# 6_channel_esp32_energy_meter_add-on.net
KiCad netlist of a schematic drawn in EAGLE
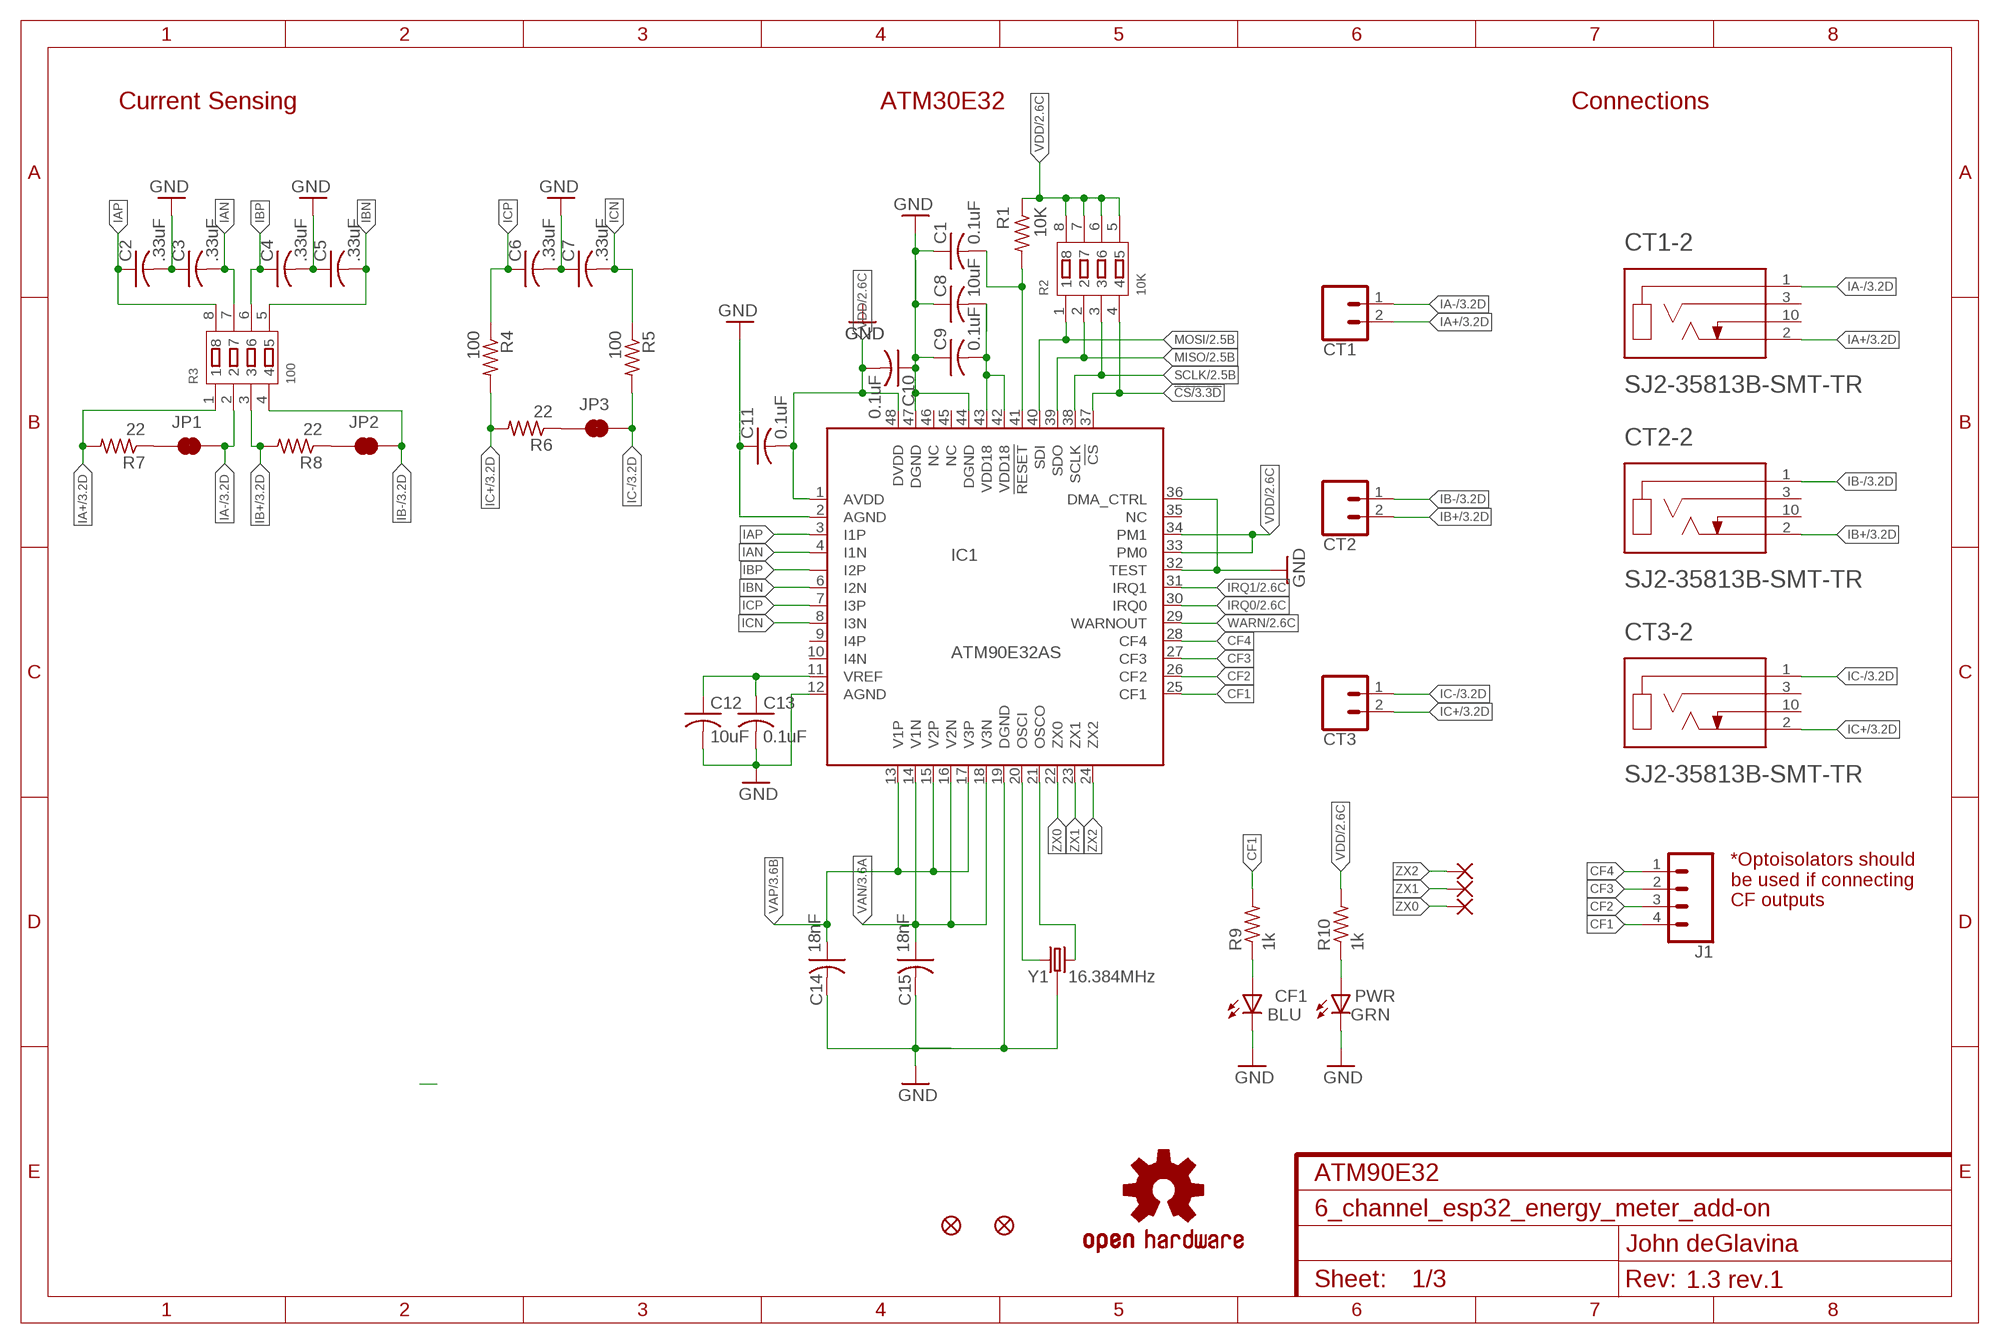
[diagram p0: schematic, sheet 1]
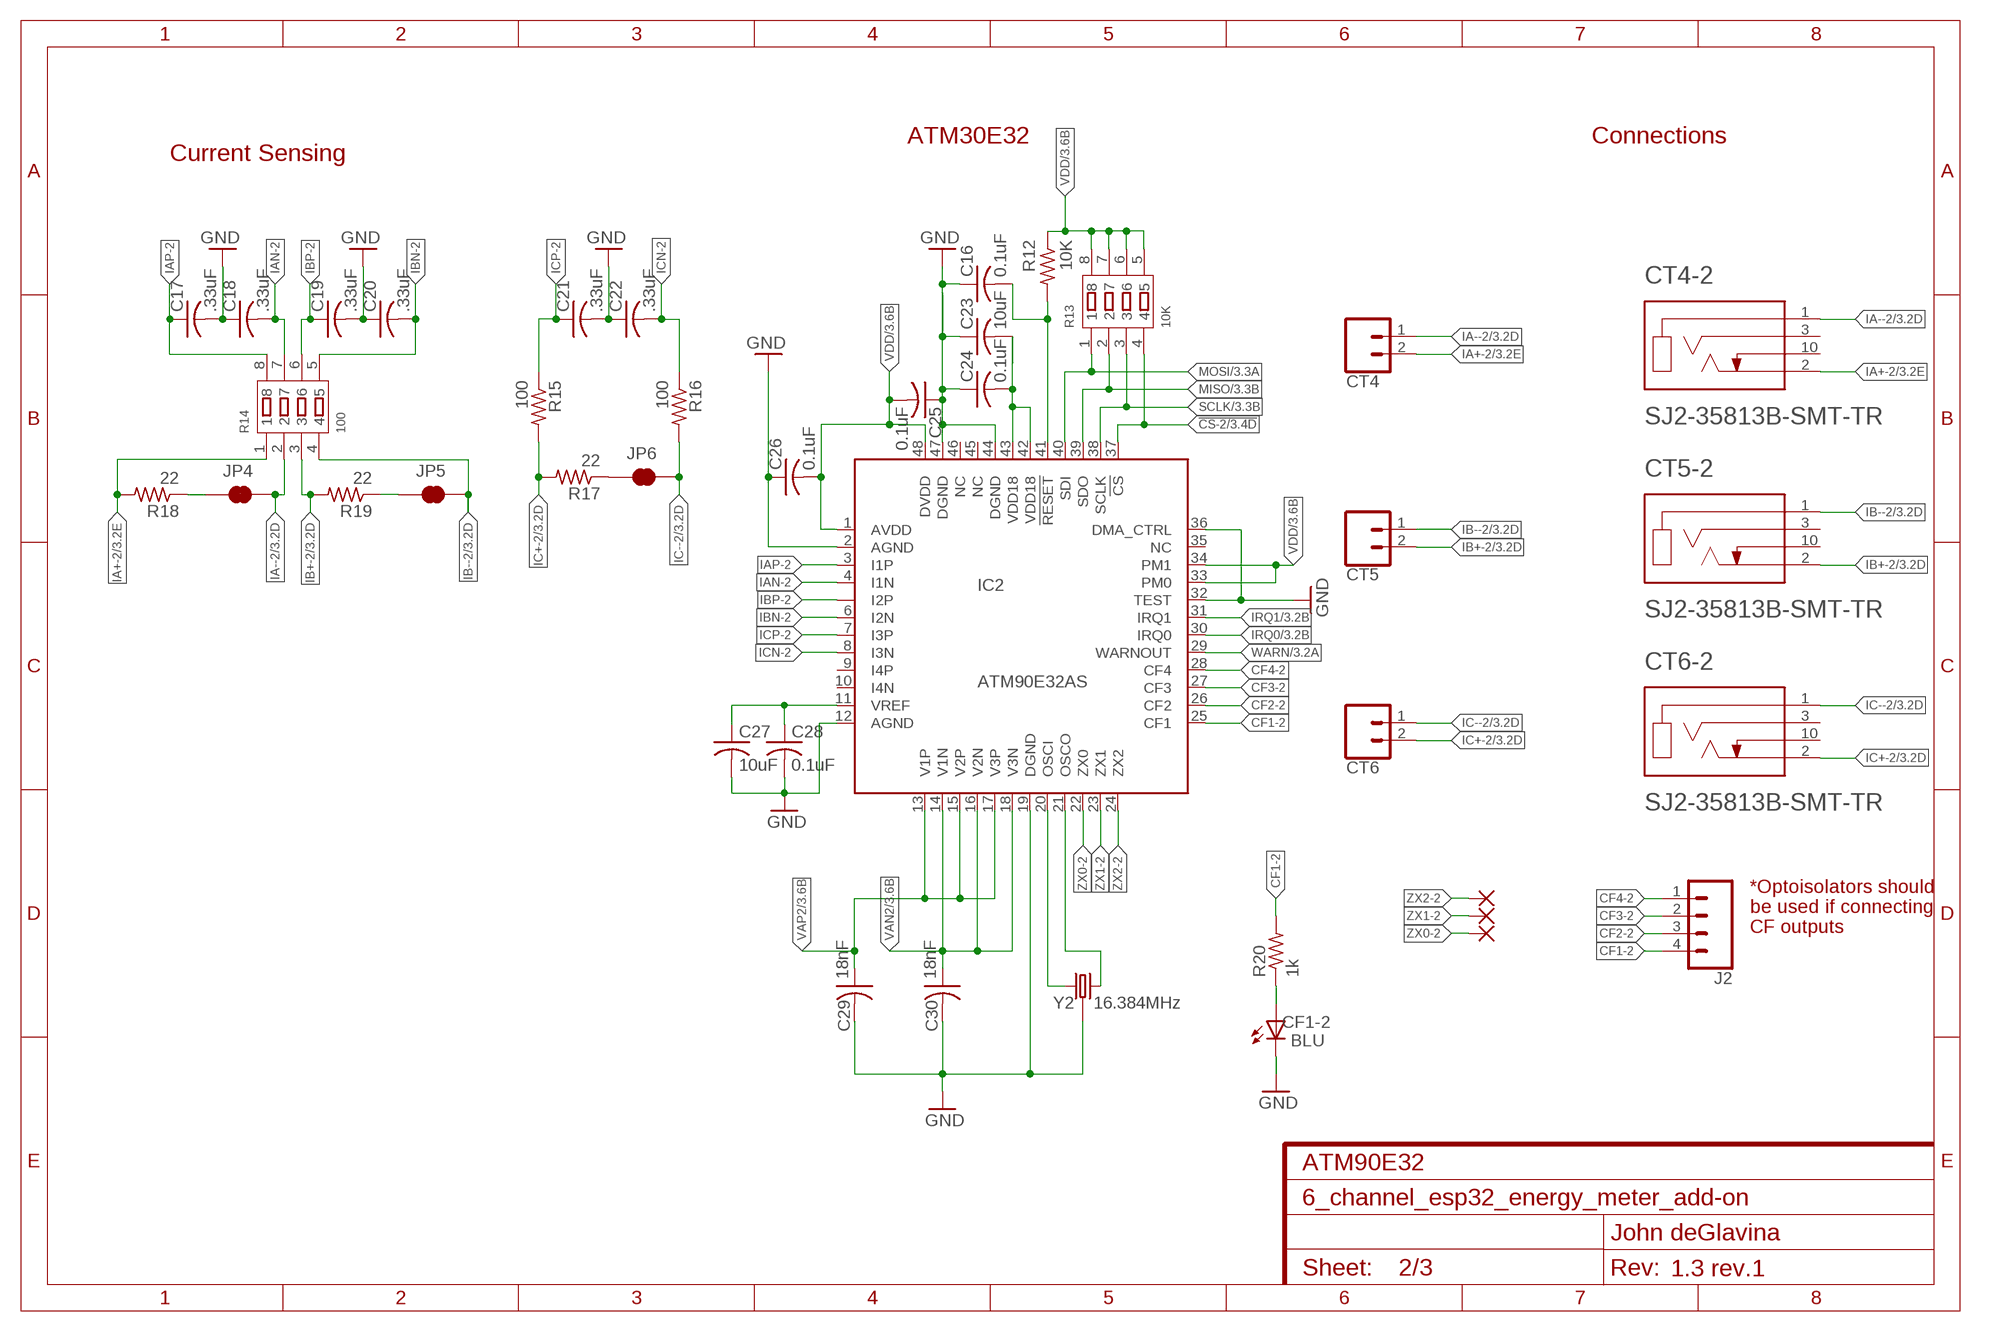
[diagram p1: schematic, sheet 2]
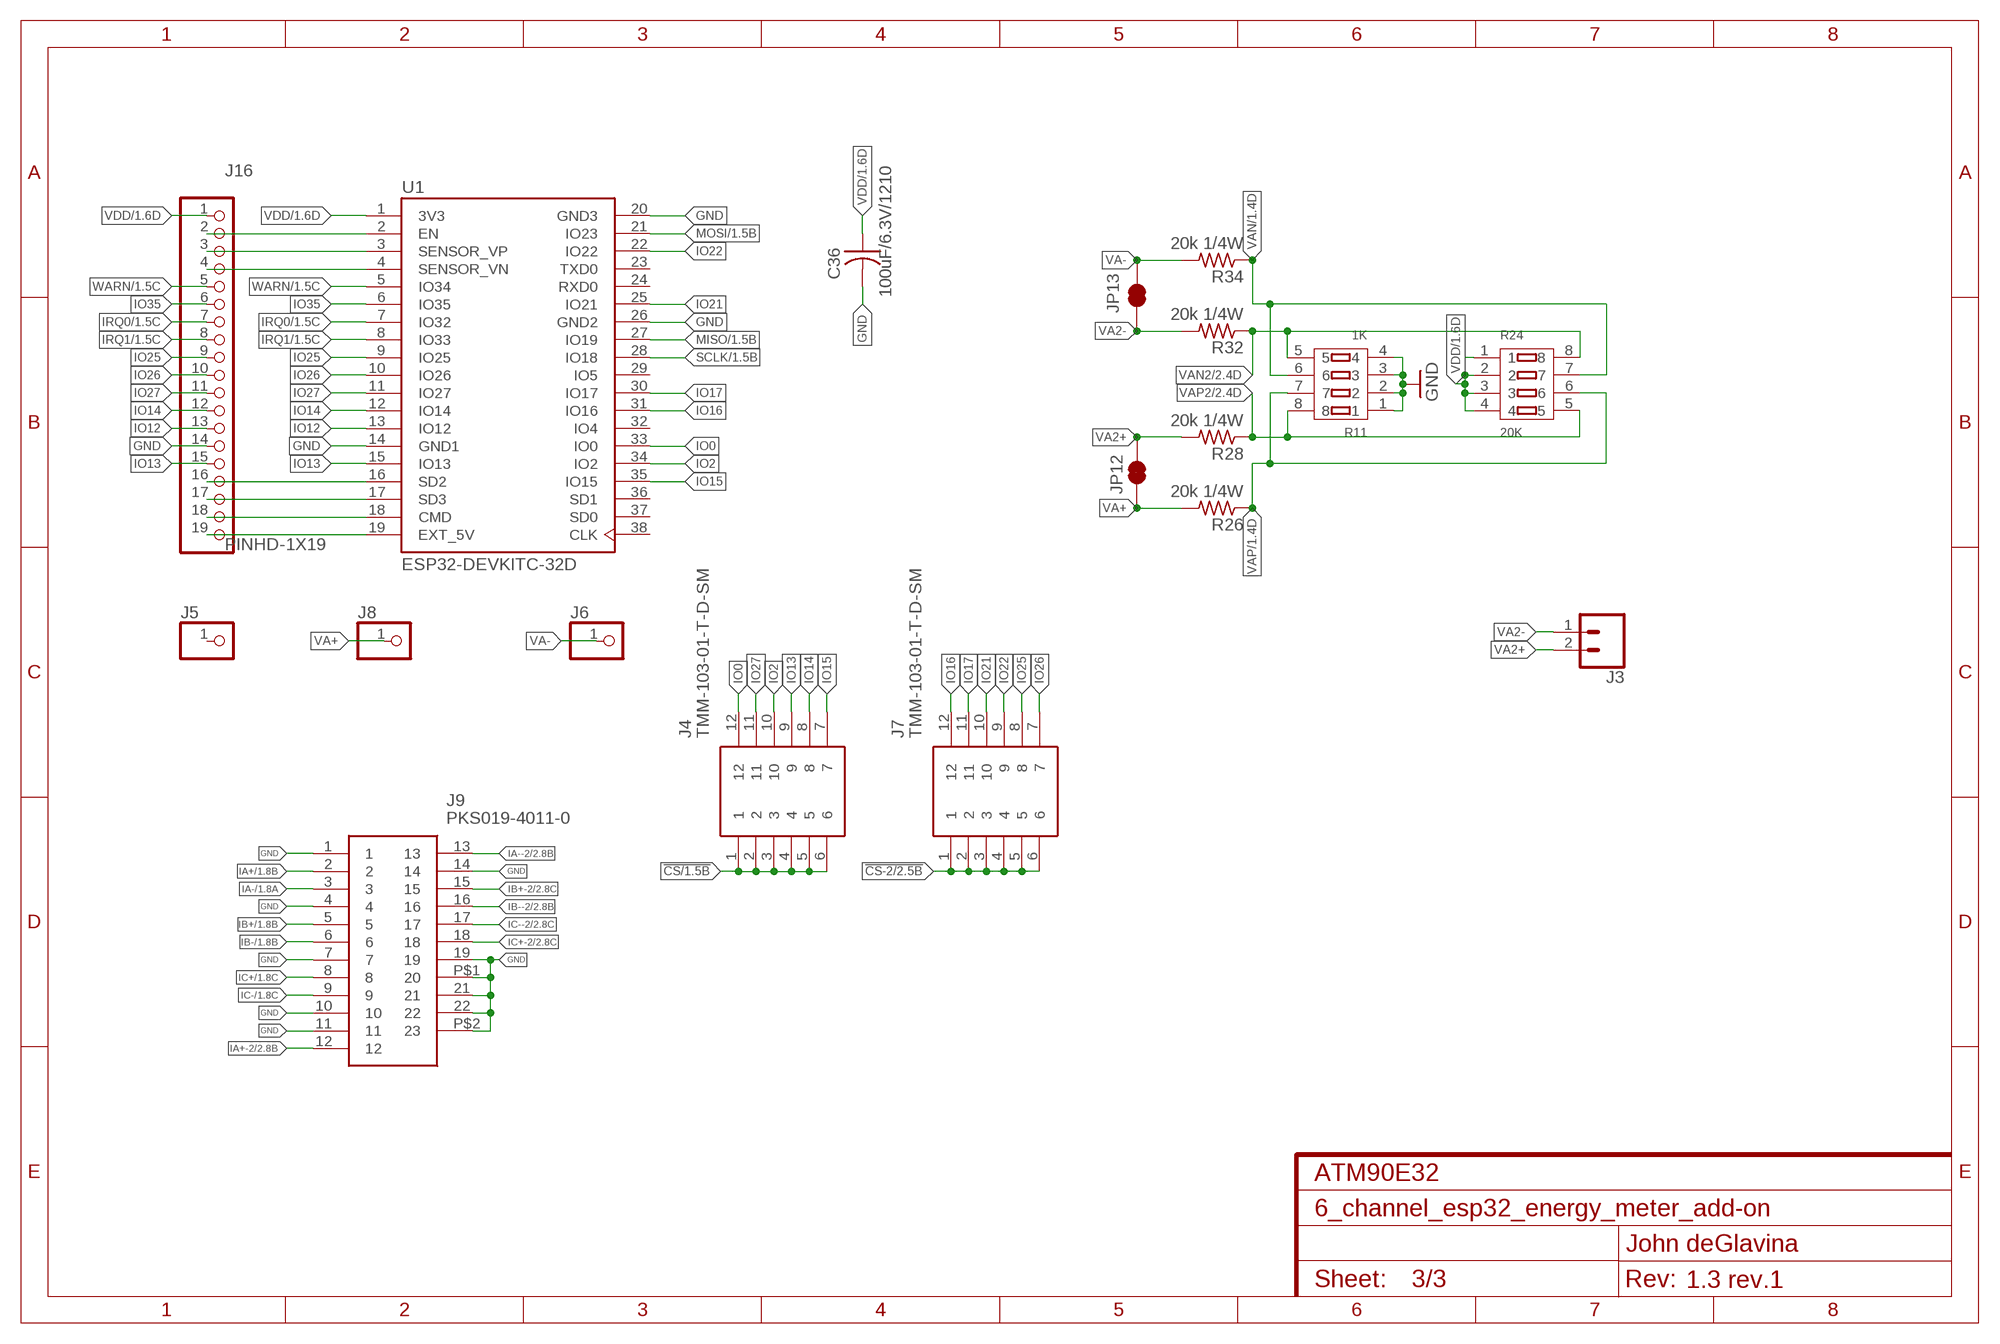
[diagram p2: schematic, sheet 3]

(export (version "E")
  (design (tool "Eeschema 10.0.6"))
  (components
    (comp (ref "C16")
      (value "0.1uF")
      (footprint "eagle-import:C0603")
      (libsource (lib "eagle-import") (part "C-USC0603"))
    )
    (comp (ref "C17")
      (value ".33uF")
      (footprint "eagle-import:C0603")
      (libsource (lib "eagle-import") (part "C-USC0603"))
    )
    (comp (ref "C18")
      (value ".33uF")
      (footprint "eagle-import:C0603")
      (libsource (lib "eagle-import") (part "C-USC0603"))
    )
    (comp (ref "C19")
      (value ".33uF")
      (footprint "eagle-import:C0603")
      (libsource (lib "eagle-import") (part "C-USC0603"))
    )
    (comp (ref "C20")
      (value ".33uF")
      (footprint "eagle-import:C0603")
      (libsource (lib "eagle-import") (part "C-USC0603"))
    )
    (comp (ref "C21")
      (value ".33uF")
      (footprint "eagle-import:C0603")
      (libsource (lib "eagle-import") (part "C-USC0603"))
    )
    (comp (ref "C22")
      (value ".33uF")
      (footprint "eagle-import:C0603")
      (libsource (lib "eagle-import") (part "C-USC0603"))
    )
    (comp (ref "C23")
      (value "10uF")
      (footprint "eagle-import:C0603")
      (libsource (lib "eagle-import") (part "C-USC0603"))
    )
    (comp (ref "C24")
      (value "0.1uF")
      (footprint "eagle-import:C0603")
      (libsource (lib "eagle-import") (part "C-USC0603"))
    )
    (comp (ref "C25")
      (value "0.1uF")
      (footprint "eagle-import:C0603")
      (libsource (lib "eagle-import") (part "C-USC0603"))
    )
    (comp (ref "C26")
      (value "0.1uF")
      (footprint "eagle-import:C0603")
      (libsource (lib "eagle-import") (part "C-USC0603"))
    )
    (comp (ref "C27")
      (value "10uF")
      (footprint "eagle-import:C0603")
      (libsource (lib "eagle-import") (part "C-USC0603"))
    )
    (comp (ref "C28")
      (value "0.1uF")
      (footprint "eagle-import:C0603")
      (libsource (lib "eagle-import") (part "C-USC0603"))
    )
    (comp (ref "C29")
      (value "18nF")
      (footprint "eagle-import:C0603")
      (libsource (lib "eagle-import") (part "C-USC0603"))
    )
    (comp (ref "C30")
      (value "18nF")
      (footprint "eagle-import:C0603")
      (libsource (lib "eagle-import") (part "C-USC0603"))
    )
    (comp (ref "CF1-2")
      (value "BLU")
      (footprint "eagle-import:CHIPLED_0603")
      (libsource (lib "eagle-import") (part "LEDCHIPLED_0603"))
    )
    (comp (ref "CT4")
      (value "CONN_023.5MM")
      (footprint "eagle-import:SCREWTERMINAL-3.5MM-2")
      (libsource (lib "eagle-import") (part "SparkFun-Connectors_8231346_CONN_023.5MM"))
    )
    (comp (ref "CT4-2")
      (value "SJ2-35813B-SMT-TR")
      (footprint "eagle-import:CUI_SJ2-35813B-SMT-TR")
      (fields (field (name "MANUFACTURER") "CUI"))
      (libsource (lib "eagle-import") (part "SJ2-35813B-SMT-TR"))
    )
    (comp (ref "CT5")
      (value "CONN_023.5MM")
      (footprint "eagle-import:SCREWTERMINAL-3.5MM-2")
      (libsource (lib "eagle-import") (part "SparkFun-Connectors_8231346_CONN_023.5MM"))
    )
    (comp (ref "CT5-2")
      (value "SJ2-35813B-SMT-TR")
      (footprint "eagle-import:CUI_SJ2-35813B-SMT-TR")
      (fields (field (name "MANUFACTURER") "CUI"))
      (libsource (lib "eagle-import") (part "SJ2-35813B-SMT-TR"))
    )
    (comp (ref "CT6")
      (value "CONN_023.5MM")
      (footprint "eagle-import:SCREWTERMINAL-3.5MM-2")
      (libsource (lib "eagle-import") (part "SparkFun-Connectors_8231346_CONN_023.5MM"))
    )
    (comp (ref "CT6-2")
      (value "SJ2-35813B-SMT-TR")
      (footprint "eagle-import:CUI_SJ2-35813B-SMT-TR")
      (fields (field (name "MANUFACTURER") "CUI"))
      (libsource (lib "eagle-import") (part "SJ2-35813B-SMT-TR"))
    )
    (comp (ref "IC2")
      (value "ATM90E32AS")
      (footprint "eagle-import:QFP50P900X900X120-48")
      (fields (field (name "SPICEPREFIX") "X"))
      (libsource (lib "eagle-import") (part "ATM90E36"))
    )
    (comp (ref "J2")
      (value "CONN_04")
      (footprint "eagle-import:1X04")
      (libsource (lib "eagle-import") (part "CONN_04"))
    )
    (comp (ref "JP4")
      (value "JUMPER-SMT_2_NC_TRACE_SILK")
      (footprint "eagle-import:SMT-JUMPER_2_NC_TRACE_SILK")
      (libsource (lib "eagle-import") (part "JUMPER-SMT_2_NC_TRACE_SILK"))
    )
    (comp (ref "JP5")
      (value "JUMPER-SMT_2_NC_TRACE_SILK")
      (footprint "eagle-import:SMT-JUMPER_2_NC_TRACE_SILK")
      (libsource (lib "eagle-import") (part "JUMPER-SMT_2_NC_TRACE_SILK"))
    )
    (comp (ref "JP6")
      (value "JUMPER-SMT_2_NC_TRACE_SILK")
      (footprint "eagle-import:SMT-JUMPER_2_NC_TRACE_SILK")
      (libsource (lib "eagle-import") (part "JUMPER-SMT_2_NC_TRACE_SILK"))
    )
    (comp (ref "R12")
      (value "10K")
      (footprint "eagle-import:R0603")
      (libsource (lib "eagle-import") (part "R-US_R0603"))
    )
    (comp (ref "R13")
      (value "10K")
      (footprint "eagle-import:RA1206-8")
      (fields (field (name "MPN") "Chip-Array-Series-1%"))
      (libsource (lib "eagle-import") (part "SMD-RES-ARRAY-1K-4R(RA1206-8)"))
    )
    (comp (ref "R14")
      (value "100")
      (footprint "eagle-import:RA1206-8")
      (fields (field (name "MPN") "Chip-Array-Series-1%"))
      (libsource (lib "eagle-import") (part "SMD-RES-ARRAY-1K-4R(RA1206-8)"))
    )
    (comp (ref "R15")
      (value "100")
      (footprint "eagle-import:R0603")
      (libsource (lib "eagle-import") (part "R-US_R0603"))
    )
    (comp (ref "R16")
      (value "100")
      (footprint "eagle-import:R0603")
      (libsource (lib "eagle-import") (part "R-US_R0603"))
    )
    (comp (ref "R17")
      (value "22")
      (footprint "eagle-import:R0603")
      (libsource (lib "eagle-import") (part "R-US_R0603"))
    )
    (comp (ref "R18")
      (value "22")
      (footprint "eagle-import:R0603")
      (libsource (lib "eagle-import") (part "R-US_R0603"))
    )
    (comp (ref "R19")
      (value "22")
      (footprint "eagle-import:R0603")
      (libsource (lib "eagle-import") (part "R-US_R0603"))
    )
    (comp (ref "R20")
      (value "1k")
      (footprint "eagle-import:R0603")
      (libsource (lib "eagle-import") (part "R-US_R0603"))
    )
    (comp (ref "Y2")
      (value "16.384MHz")
      (footprint "eagle-import:CRYSTAL-SMD-3.2X2.5MM")
      (libsource (lib "eagle-import") (part "CRYSTAL-GROUNDEDSMD-3.2X2.5"))
    )
    (comp (ref "ZX0-2")
      (value "WIREPADSMD1,27-254")
      (footprint "eagle-import:SMD1,27-2,54")
      (libsource (lib "eagle-import") (part "WIREPADSMD1,27-254"))
    )
    (comp (ref "ZX1-2")
      (value "WIREPADSMD1,27-254")
      (footprint "eagle-import:SMD1,27-2,54")
      (libsource (lib "eagle-import") (part "WIREPADSMD1,27-254"))
    )
    (comp (ref "ZX2-2")
      (value "WIREPADSMD1,27-254")
      (footprint "eagle-import:SMD1,27-2,54")
      (libsource (lib "eagle-import") (part "WIREPADSMD1,27-254"))
    )
    (comp (ref "C36")
      (value "100uF/6.3V/1210")
      (footprint "eagle-import:C1210")
      (libsource (lib "eagle-import") (part "C-USC1210"))
    )
    (comp (ref "J3")
      (value "CONN_023.5MM")
      (footprint "eagle-import:SCREWTERMINAL-3.5MM-2")
      (libsource (lib "eagle-import") (part "CONN_023.5MM"))
    )
    (comp (ref "J4")
      (value "TMM-103-01-T-D-SM")
      (footprint "eagle-import:SOP200P706X597-12N")
      (libsource (lib "eagle-import") (part "TMM-103-01-T-D-SM"))
    )
    (comp (ref "J5")
      (value "PINHD1X1-SM1X01_SM")
      (footprint "eagle-import:1X01-SM")
      (libsource (lib "eagle-import") (part "PINHD1X1-SM1X01_SM"))
    )
    (comp (ref "J6")
      (value "PINHD1X1-SM1X01_SM")
      (footprint "eagle-import:1X01-SM")
      (libsource (lib "eagle-import") (part "PINHD1X1-SM1X01_SM"))
    )
    (comp (ref "J7")
      (value "TMM-103-01-T-D-SM")
      (footprint "eagle-import:SOP200P706X597-12N")
      (libsource (lib "eagle-import") (part "TMM-103-01-T-D-SM"))
    )
    (comp (ref "J8")
      (value "PINHD1X1-SM1X01_SM")
      (footprint "eagle-import:1X01-SM")
      (libsource (lib "eagle-import") (part "PINHD1X1-SM1X01_SM"))
    )
    (comp (ref "J9")
      (value "PKS019-4011-0")
      (footprint "eagle-import:PKS01940110")
      (fields (field (name "MOUSER_PART_NUMBER") "945-PKS019-4011-0"))
      (libsource (lib "eagle-import") (part "PKS019-4011-0"))
    )
    (comp (ref "J16")
      (value "PINHD-1X19")
      (footprint "eagle-import:1X19")
      (fields (field (name "SPICEPREFIX") "X"))
      (libsource (lib "eagle-import") (part "PINHD-1X19"))
    )
    (comp (ref "JP12")
      (value "JUMPER-SMT_2_NC_TRACE_SILK")
      (footprint "eagle-import:SMT-JUMPER_2_NC_TRACE_SILK")
      (libsource (lib "eagle-import") (part "JUMPER-SMT_2_NC_TRACE_SILK"))
    )
    (comp (ref "JP13")
      (value "JUMPER-SMT_2_NC_TRACE_SILK")
      (footprint "eagle-import:SMT-JUMPER_2_NC_TRACE_SILK")
      (libsource (lib "eagle-import") (part "JUMPER-SMT_2_NC_TRACE_SILK"))
    )
    (comp (ref "R11")
      (value "1K")
      (footprint "eagle-import:RA1206-8")
      (fields (field (name "MPN") "Chip-Array-Series-1%"))
      (libsource (lib "eagle-import") (part "SMD-RES-ARRAY-1K-4R(RA1206-8)"))
    )
    (comp (ref "R24")
      (value "20K")
      (footprint "eagle-import:RA1206-8")
      (fields (field (name "MPN") "Chip-Array-Series-1%"))
      (libsource (lib "eagle-import") (part "SMD-RES-ARRAY-1K-4R(RA1206-8)"))
    )
    (comp (ref "R26")
      (value "20k 1/4W")
      (footprint "eagle-import:R0603")
      (libsource (lib "eagle-import") (part "R-US_R0603"))
    )
    (comp (ref "R28")
      (value "20k 1/4W")
      (footprint "eagle-import:R0603")
      (libsource (lib "eagle-import") (part "R-US_R0603"))
    )
    (comp (ref "R32")
      (value "20k 1/4W")
      (footprint "eagle-import:R0603")
      (libsource (lib "eagle-import") (part "R-US_R0603"))
    )
    (comp (ref "R34")
      (value "20k 1/4W")
      (footprint "eagle-import:R0603")
      (libsource (lib "eagle-import") (part "R-US_R0603"))
    )
    (comp (ref "U1")
      (value "ESP32-DEVKITC-32D")
      (footprint "eagle-import:MODULE_ESP32-DEVKITC-32D")
      (fields (field (name "MF") "Espressif Systems"))
      (libsource (lib "eagle-import") (part "ESP32-DEVKITC-32D"))
    )
    (comp (ref "C1")
      (value "0.1uF")
      (footprint "eagle-import:C0603")
      (libsource (lib "eagle-import") (part "C-USC0603"))
    )
    (comp (ref "C2")
      (value ".33uF")
      (footprint "eagle-import:C0603")
      (libsource (lib "eagle-import") (part "C-USC0603"))
    )
    (comp (ref "C3")
      (value ".33uF")
      (footprint "eagle-import:C0603")
      (libsource (lib "eagle-import") (part "C-USC0603"))
    )
    (comp (ref "C4")
      (value ".33uF")
      (footprint "eagle-import:C0603")
      (libsource (lib "eagle-import") (part "C-USC0603"))
    )
    (comp (ref "C5")
      (value ".33uF")
      (footprint "eagle-import:C0603")
      (libsource (lib "eagle-import") (part "C-USC0603"))
    )
    (comp (ref "C6")
      (value ".33uF")
      (footprint "eagle-import:C0603")
      (libsource (lib "eagle-import") (part "C-USC0603"))
    )
    (comp (ref "C7")
      (value ".33uF")
      (footprint "eagle-import:C0603")
      (libsource (lib "eagle-import") (part "C-USC0603"))
    )
    (comp (ref "C8")
      (value "10uF")
      (footprint "eagle-import:C0603")
      (libsource (lib "eagle-import") (part "C-USC0603"))
    )
    (comp (ref "C9")
      (value "0.1uF")
      (footprint "eagle-import:C0603")
      (libsource (lib "eagle-import") (part "C-USC0603"))
    )
    (comp (ref "C10")
      (value "0.1uF")
      (footprint "eagle-import:C0603")
      (libsource (lib "eagle-import") (part "C-USC0603"))
    )
    (comp (ref "C11")
      (value "0.1uF")
      (footprint "eagle-import:C0603")
      (libsource (lib "eagle-import") (part "C-USC0603"))
    )
    (comp (ref "C12")
      (value "10uF")
      (footprint "eagle-import:C0603")
      (libsource (lib "eagle-import") (part "C-USC0603"))
    )
    (comp (ref "C13")
      (value "0.1uF")
      (footprint "eagle-import:C0603")
      (libsource (lib "eagle-import") (part "C-USC0603"))
    )
    (comp (ref "C14")
      (value "18nF")
      (footprint "eagle-import:C0603")
      (libsource (lib "eagle-import") (part "C-USC0603"))
    )
    (comp (ref "C15")
      (value "18nF")
      (footprint "eagle-import:C0603")
      (libsource (lib "eagle-import") (part "C-USC0603"))
    )
    (comp (ref "CF1")
      (value "BLU")
      (footprint "eagle-import:CHIPLED_0603")
      (libsource (lib "eagle-import") (part "LEDCHIPLED_0603"))
    )
    (comp (ref "CT1")
      (value "CONN_023.5MM")
      (footprint "eagle-import:SCREWTERMINAL-3.5MM-2")
      (libsource (lib "eagle-import") (part "SparkFun-Connectors_8231346_CONN_023.5MM"))
    )
    (comp (ref "CT1-2")
      (value "SJ2-35813B-SMT-TR")
      (footprint "eagle-import:CUI_SJ2-35813B-SMT-TR")
      (fields (field (name "MANUFACTURER") "CUI"))
      (libsource (lib "eagle-import") (part "SJ2-35813B-SMT-TR"))
    )
    (comp (ref "CT2")
      (value "CONN_023.5MM")
      (footprint "eagle-import:SCREWTERMINAL-3.5MM-2")
      (libsource (lib "eagle-import") (part "SparkFun-Connectors_8231346_CONN_023.5MM"))
    )
    (comp (ref "CT2-2")
      (value "SJ2-35813B-SMT-TR")
      (footprint "eagle-import:CUI_SJ2-35813B-SMT-TR")
      (fields (field (name "MANUFACTURER") "CUI"))
      (libsource (lib "eagle-import") (part "SJ2-35813B-SMT-TR"))
    )
    (comp (ref "CT3")
      (value "CONN_023.5MM")
      (footprint "eagle-import:SCREWTERMINAL-3.5MM-2")
      (libsource (lib "eagle-import") (part "SparkFun-Connectors_8231346_CONN_023.5MM"))
    )
    (comp (ref "CT3-2")
      (value "SJ2-35813B-SMT-TR")
      (footprint "eagle-import:CUI_SJ2-35813B-SMT-TR")
      (fields (field (name "MANUFACTURER") "CUI"))
      (libsource (lib "eagle-import") (part "SJ2-35813B-SMT-TR"))
    )
    (comp (ref "FD1")
      (value "FIDUCIALUFIDUCIAL")
      (footprint "eagle-import:FIDUCIAL-MICRO")
      (libsource (lib "eagle-import") (part "FIDUCIALUFIDUCIAL"))
    )
    (comp (ref "FD2")
      (value "FIDUCIALUFIDUCIAL")
      (footprint "eagle-import:FIDUCIAL-MICRO")
      (libsource (lib "eagle-import") (part "FIDUCIALUFIDUCIAL"))
    )
    (comp (ref "IC1")
      (value "ATM90E32AS")
      (footprint "eagle-import:QFP50P900X900X120-48")
      (fields (field (name "SPICEPREFIX") "X"))
      (libsource (lib "eagle-import") (part "ATM90E36"))
    )
    (comp (ref "J1")
      (value "CONN_04")
      (footprint "eagle-import:1X04")
      (libsource (lib "eagle-import") (part "CONN_04"))
    )
    (comp (ref "JP1")
      (value "JUMPER-SMT_2_NC_TRACE_SILK")
      (footprint "eagle-import:SMT-JUMPER_2_NC_TRACE_SILK")
      (libsource (lib "eagle-import") (part "JUMPER-SMT_2_NC_TRACE_SILK"))
    )
    (comp (ref "JP2")
      (value "JUMPER-SMT_2_NC_TRACE_SILK")
      (footprint "eagle-import:SMT-JUMPER_2_NC_TRACE_SILK")
      (libsource (lib "eagle-import") (part "JUMPER-SMT_2_NC_TRACE_SILK"))
    )
    (comp (ref "JP3")
      (value "JUMPER-SMT_2_NC_TRACE_SILK")
      (footprint "eagle-import:SMT-JUMPER_2_NC_TRACE_SILK")
      (libsource (lib "eagle-import") (part "JUMPER-SMT_2_NC_TRACE_SILK"))
    )
    (comp (ref "LOGO1")
      (value "OSHW-LOGOS")
      (footprint "eagle-import:OSHW-LOGO-S")
      (libsource (lib "eagle-import") (part "OSHW-LOGOS"))
    )
    (comp (ref "PWR")
      (value "GRN")
      (footprint "eagle-import:CHIPLED_0603")
      (libsource (lib "eagle-import") (part "LEDCHIPLED_0603"))
    )
    (comp (ref "R1")
      (value "10K")
      (footprint "eagle-import:R0603")
      (libsource (lib "eagle-import") (part "R-US_R0603"))
    )
    (comp (ref "R2")
      (value "10K")
      (footprint "eagle-import:RA1206-8")
      (fields (field (name "MPN") "Chip-Array-Series-1%"))
      (libsource (lib "eagle-import") (part "SMD-RES-ARRAY-1K-4R(RA1206-8)"))
    )
    (comp (ref "R3")
      (value "100")
      (footprint "eagle-import:RA1206-8")
      (fields (field (name "MPN") "Chip-Array-Series-1%"))
      (libsource (lib "eagle-import") (part "SMD-RES-ARRAY-1K-4R(RA1206-8)"))
    )
    (comp (ref "R4")
      (value "100")
      (footprint "eagle-import:R0603")
      (libsource (lib "eagle-import") (part "R-US_R0603"))
    )
    (comp (ref "R5")
      (value "100")
      (footprint "eagle-import:R0603")
      (libsource (lib "eagle-import") (part "R-US_R0603"))
    )
    (comp (ref "R6")
      (value "22")
      (footprint "eagle-import:R0603")
      (libsource (lib "eagle-import") (part "R-US_R0603"))
    )
    (comp (ref "R7")
      (value "22")
      (footprint "eagle-import:R0603")
      (libsource (lib "eagle-import") (part "R-US_R0603"))
    )
    (comp (ref "R8")
      (value "22")
      (footprint "eagle-import:R0603")
      (libsource (lib "eagle-import") (part "R-US_R0603"))
    )
    (comp (ref "R9")
      (value "1k")
      (footprint "eagle-import:R0603")
      (libsource (lib "eagle-import") (part "R-US_R0603"))
    )
    (comp (ref "R10")
      (value "1k")
      (footprint "eagle-import:R0603")
      (libsource (lib "eagle-import") (part "R-US_R0603"))
    )
    (comp (ref "Y1")
      (value "16.384MHz")
      (footprint "eagle-import:CRYSTAL-SMD-3.2X2.5MM")
      (libsource (lib "eagle-import") (part "CRYSTAL-GROUNDEDSMD-3.2X2.5"))
    )
    (comp (ref "ZX0")
      (value "WIREPADSMD1,27-254")
      (footprint "eagle-import:SMD1,27-2,54")
      (libsource (lib "eagle-import") (part "WIREPADSMD1,27-254"))
    )
    (comp (ref "ZX1")
      (value "WIREPADSMD1,27-254")
      (footprint "eagle-import:SMD1,27-2,54")
      (libsource (lib "eagle-import") (part "WIREPADSMD1,27-254"))
    )
    (comp (ref "ZX2")
      (value "WIREPADSMD1,27-254")
      (footprint "eagle-import:SMD1,27-2,54")
      (libsource (lib "eagle-import") (part "WIREPADSMD1,27-254"))
    )
  )
  (nets
    (net (code "1") (name "CF1") (class "Default")
      (node (ref "IC1") (pin "25") (pinfunction "CF1_25") (pintype "output"))
      (node (ref "J1") (pin "4") (pinfunction "4_4") (pintype "passive"))
      (node (ref "R9") (pin "2") (pinfunction "2_2") (pintype "passive"))
    )
    (net (code "2") (name "CF1-2") (class "Default")
      (node (ref "IC2") (pin "25") (pinfunction "CF1_25") (pintype "output"))
      (node (ref "J2") (pin "4") (pinfunction "4_4") (pintype "passive"))
      (node (ref "R20") (pin "2") (pinfunction "2_2") (pintype "passive"))
    )
    (net (code "3") (name "CF2") (class "Default")
      (node (ref "IC1") (pin "26") (pinfunction "CF2_26") (pintype "output"))
      (node (ref "J1") (pin "3") (pinfunction "3_3") (pintype "passive"))
    )
    (net (code "4") (name "CF2-2") (class "Default")
      (node (ref "IC2") (pin "26") (pinfunction "CF2_26") (pintype "output"))
      (node (ref "J2") (pin "3") (pinfunction "3_3") (pintype "passive"))
    )
    (net (code "5") (name "CF3") (class "Default")
      (node (ref "IC1") (pin "27") (pinfunction "CF3_27") (pintype "output"))
      (node (ref "J1") (pin "2") (pinfunction "2_2") (pintype "passive"))
    )
    (net (code "6") (name "CF3-2") (class "Default")
      (node (ref "IC2") (pin "27") (pinfunction "CF3_27") (pintype "output"))
      (node (ref "J2") (pin "2") (pinfunction "2_2") (pintype "passive"))
    )
    (net (code "7") (name "CF4") (class "Default")
      (node (ref "IC1") (pin "28") (pinfunction "CF4_28") (pintype "output"))
      (node (ref "J1") (pin "1") (pinfunction "1_1") (pintype "passive"))
    )
    (net (code "8") (name "CF4-2") (class "Default")
      (node (ref "IC2") (pin "28") (pinfunction "CF4_28") (pintype "output"))
      (node (ref "J2") (pin "1") (pinfunction "1_1") (pintype "passive"))
    )
    (net (code "9") (name "GND") (class "Default")
      (node (ref "C1") (pin "1") (pinfunction "1_1") (pintype "passive"))
      (node (ref "C10") (pin "1") (pinfunction "1_1") (pintype "passive"))
      (node (ref "C11") (pin "1") (pinfunction "1_1") (pintype "passive"))
      (node (ref "C12") (pin "2") (pinfunction "2_2") (pintype "passive"))
      (node (ref "C13") (pin "2") (pinfunction "2_2") (pintype "passive"))
      (node (ref "C14") (pin "2") (pinfunction "2_2") (pintype "passive"))
      (node (ref "C15") (pin "2") (pinfunction "2_2") (pintype "passive"))
      (node (ref "C16") (pin "1") (pinfunction "1_1") (pintype "passive"))
      (node (ref "C17") (pin "2") (pinfunction "2_2") (pintype "passive"))
      (node (ref "C18") (pin "1") (pinfunction "1_1") (pintype "passive"))
      (node (ref "C19") (pin "2") (pinfunction "2_2") (pintype "passive"))
      (node (ref "C2") (pin "2") (pinfunction "2_2") (pintype "passive"))
      (node (ref "C20") (pin "1") (pinfunction "1_1") (pintype "passive"))
      (node (ref "C21") (pin "2") (pinfunction "2_2") (pintype "passive"))
      (node (ref "C22") (pin "1") (pinfunction "1_1") (pintype "passive"))
      (node (ref "C23") (pin "1") (pinfunction "1_1") (pintype "passive"))
      (node (ref "C24") (pin "1") (pinfunction "1_1") (pintype "passive"))
      (node (ref "C25") (pin "1") (pinfunction "1_1") (pintype "passive"))
      (node (ref "C26") (pin "1") (pinfunction "1_1") (pintype "passive"))
      (node (ref "C27") (pin "2") (pinfunction "2_2") (pintype "passive"))
      (node (ref "C28") (pin "2") (pinfunction "2_2") (pintype "passive"))
      (node (ref "C29") (pin "2") (pinfunction "2_2") (pintype "passive"))
      (node (ref "C3") (pin "1") (pinfunction "1_1") (pintype "passive"))
      (node (ref "C30") (pin "2") (pinfunction "2_2") (pintype "passive"))
      (node (ref "C36") (pin "2") (pinfunction "2_2") (pintype "passive"))
      (node (ref "C4") (pin "2") (pinfunction "2_2") (pintype "passive"))
      (node (ref "C5") (pin "1") (pinfunction "1_1") (pintype "passive"))
      (node (ref "C6") (pin "2") (pinfunction "2_2") (pintype "passive"))
      (node (ref "C7") (pin "1") (pinfunction "1_1") (pintype "passive"))
      (node (ref "C8") (pin "1") (pinfunction "1_1") (pintype "passive"))
      (node (ref "C9") (pin "1") (pinfunction "1_1") (pintype "passive"))
      (node (ref "CF1") (pin "C") (pinfunction "C_C") (pintype "passive"))
      (node (ref "CF1-2") (pin "C") (pinfunction "C_C") (pintype "passive"))
      (node (ref "IC1") (pin "12") (pinfunction "AGND_12") (pintype "power_in"))
      (node (ref "IC1") (pin "19") (pinfunction "DGND_19") (pintype "power_in"))
      (node (ref "IC1") (pin "2") (pinfunction "AGND_2") (pintype "power_in"))
      (node (ref "IC1") (pin "32") (pinfunction "TEST_32") (pintype "power_in"))
      (node (ref "IC1") (pin "36") (pinfunction "DMA_CTRL_36") (pintype "input"))
      (node (ref "IC1") (pin "44") (pinfunction "DGND_44") (pintype "power_in"))
      (node (ref "IC1") (pin "47") (pinfunction "DGND_47") (pintype "power_in"))
      (node (ref "IC2") (pin "12") (pinfunction "AGND_12") (pintype "power_in"))
      (node (ref "IC2") (pin "19") (pinfunction "DGND_19") (pintype "power_in"))
      (node (ref "IC2") (pin "2") (pinfunction "AGND_2") (pintype "power_in"))
      (node (ref "IC2") (pin "32") (pinfunction "TEST_32") (pintype "power_in"))
      (node (ref "IC2") (pin "36") (pinfunction "DMA_CTRL_36") (pintype "input"))
      (node (ref "IC2") (pin "44") (pinfunction "DGND_44") (pintype "power_in"))
      (node (ref "IC2") (pin "47") (pinfunction "DGND_47") (pintype "power_in"))
      (node (ref "J16") (pin "14") (pinfunction "14_14") (pintype "passive"))
      (node (ref "J9") (pin "1") (pinfunction "1_1") (pintype "bidirectional"))
      (node (ref "J9") (pin "10") (pinfunction "10_10") (pintype "bidirectional"))
      (node (ref "J9") (pin "11") (pinfunction "11_11") (pintype "bidirectional"))
      (node (ref "J9") (pin "14") (pinfunction "14_14") (pintype "bidirectional"))
      (node (ref "J9") (pin "19") (pinfunction "19_19") (pintype "bidirectional"))
      (node (ref "J9") (pin "21") (pinfunction "21_21") (pintype "bidirectional"))
      (node (ref "J9") (pin "22") (pinfunction "22_22") (pintype "bidirectional"))
      (node (ref "J9") (pin "4") (pinfunction "4_4") (pintype "bidirectional"))
      (node (ref "J9") (pin "7") (pinfunction "7_7") (pintype "bidirectional"))
      (node (ref "J9") (pin "P$1") (pinfunction "20_P$1") (pintype "bidirectional"))
      (node (ref "J9") (pin "P$2") (pinfunction "23_P$2") (pintype "bidirectional"))
      (node (ref "PWR") (pin "C") (pinfunction "C_C") (pintype "passive"))
      (node (ref "R11") (pin "1") (pinfunction "1_1") (pintype "bidirectional"))
      (node (ref "R11") (pin "2") (pinfunction "2_2") (pintype "bidirectional"))
      (node (ref "R11") (pin "3") (pinfunction "3_3") (pintype "bidirectional"))
      (node (ref "R11") (pin "4") (pinfunction "4_4") (pintype "bidirectional"))
      (node (ref "U1") (pin "14") (pinfunction "GND1_14") (pintype "power_in"))
      (node (ref "U1") (pin "20") (pinfunction "GND3_20") (pintype "power_in"))
      (node (ref "U1") (pin "26") (pinfunction "GND2_26") (pintype "power_in"))
      (node (ref "Y1") (pin "2") (pinfunction "3_2") (pintype "passive"))
      (node (ref "Y1") (pin "4") (pinfunction "3_4") (pintype "passive"))
      (node (ref "Y2") (pin "2") (pinfunction "3_2") (pintype "passive"))
      (node (ref "Y2") (pin "4") (pinfunction "3_4") (pintype "passive"))
    )
    (net (code "10") (name "IA+") (class "Default")
      (node (ref "CT1") (pin "2") (pinfunction "2_2") (pintype "passive"))
      (node (ref "CT1-2") (pin "2") (pinfunction "TIP_2") (pintype "passive"))
      (node (ref "J9") (pin "2") (pinfunction "2_2") (pintype "bidirectional"))
      (node (ref "R3") (pin "1") (pinfunction "1_1") (pintype "bidirectional"))
      (node (ref "R7") (pin "2") (pinfunction "2_2") (pintype "passive"))
    )
    (net (code "11") (name "IA+-2") (class "Default")
      (node (ref "CT4") (pin "2") (pinfunction "2_2") (pintype "passive"))
      (node (ref "CT4-2") (pin "2") (pinfunction "TIP_2") (pintype "passive"))
      (node (ref "J9") (pin "12") (pinfunction "12_12") (pintype "bidirectional"))
      (node (ref "R14") (pin "1") (pinfunction "1_1") (pintype "bidirectional"))
      (node (ref "R18") (pin "2") (pinfunction "2_2") (pintype "passive"))
    )
    (net (code "12") (name "IA-") (class "Default")
      (node (ref "CT1") (pin "1") (pinfunction "1_1") (pintype "passive"))
      (node (ref "CT1-2") (pin "1") (pinfunction "SLEEVE_1") (pintype "passive"))
      (node (ref "J9") (pin "3") (pinfunction "3_3") (pintype "bidirectional"))
      (node (ref "JP1") (pin "2") (pinfunction "2_2") (pintype "passive"))
      (node (ref "R3") (pin "2") (pinfunction "2_2") (pintype "bidirectional"))
    )
    (net (code "13") (name "IA--2") (class "Default")
      (node (ref "CT4") (pin "1") (pinfunction "1_1") (pintype "passive"))
      (node (ref "CT4-2") (pin "1") (pinfunction "SLEEVE_1") (pintype "passive"))
      (node (ref "J9") (pin "13") (pinfunction "13_13") (pintype "bidirectional"))
      (node (ref "JP4") (pin "2") (pinfunction "2_2") (pintype "passive"))
      (node (ref "R14") (pin "2") (pinfunction "2_2") (pintype "bidirectional"))
    )
    (net (code "14") (name "IAN") (class "Default")
      (node (ref "C3") (pin "2") (pinfunction "2_2") (pintype "passive"))
      (node (ref "IC1") (pin "4") (pinfunction "I1N_4") (pintype "input"))
      (node (ref "R3") (pin "7") (pinfunction "7_7") (pintype "bidirectional"))
    )
    (net (code "15") (name "IAN-2") (class "Default")
      (node (ref "C18") (pin "2") (pinfunction "2_2") (pintype "passive"))
      (node (ref "IC2") (pin "4") (pinfunction "I1N_4") (pintype "input"))
      (node (ref "R14") (pin "7") (pinfunction "7_7") (pintype "bidirectional"))
    )
    (net (code "16") (name "IAP") (class "Default")
      (node (ref "C2") (pin "1") (pinfunction "1_1") (pintype "passive"))
      (node (ref "IC1") (pin "3") (pinfunction "I1P_3") (pintype "input"))
      (node (ref "R3") (pin "8") (pinfunction "8_8") (pintype "bidirectional"))
    )
    (net (code "17") (name "IAP-2") (class "Default")
      (node (ref "C17") (pin "1") (pinfunction "1_1") (pintype "passive"))
      (node (ref "IC2") (pin "3") (pinfunction "I1P_3") (pintype "input"))
      (node (ref "R14") (pin "8") (pinfunction "8_8") (pintype "bidirectional"))
    )
    (net (code "18") (name "IB+") (class "Default")
      (node (ref "CT2") (pin "2") (pinfunction "2_2") (pintype "passive"))
      (node (ref "CT2-2") (pin "2") (pinfunction "TIP_2") (pintype "passive"))
      (node (ref "J9") (pin "5") (pinfunction "5_5") (pintype "bidirectional"))
      (node (ref "R3") (pin "3") (pinfunction "3_3") (pintype "bidirectional"))
      (node (ref "R8") (pin "2") (pinfunction "2_2") (pintype "passive"))
    )
    (net (code "19") (name "IB+-2") (class "Default")
      (node (ref "CT5") (pin "2") (pinfunction "2_2") (pintype "passive"))
      (node (ref "CT5-2") (pin "2") (pinfunction "TIP_2") (pintype "passive"))
      (node (ref "J9") (pin "15") (pinfunction "15_15") (pintype "bidirectional"))
      (node (ref "R14") (pin "3") (pinfunction "3_3") (pintype "bidirectional"))
      (node (ref "R19") (pin "2") (pinfunction "2_2") (pintype "passive"))
    )
    (net (code "20") (name "IB-") (class "Default")
      (node (ref "CT2") (pin "1") (pinfunction "1_1") (pintype "passive"))
      (node (ref "CT2-2") (pin "1") (pinfunction "SLEEVE_1") (pintype "passive"))
      (node (ref "J9") (pin "6") (pinfunction "6_6") (pintype "bidirectional"))
      (node (ref "JP2") (pin "2") (pinfunction "2_2") (pintype "passive"))
      (node (ref "R3") (pin "4") (pinfunction "4_4") (pintype "bidirectional"))
    )
    (net (code "21") (name "IB--2") (class "Default")
      (node (ref "CT5") (pin "1") (pinfunction "1_1") (pintype "passive"))
      (node (ref "CT5-2") (pin "1") (pinfunction "SLEEVE_1") (pintype "passive"))
      (node (ref "J9") (pin "16") (pinfunction "16_16") (pintype "bidirectional"))
      (node (ref "JP5") (pin "2") (pinfunction "2_2") (pintype "passive"))
      (node (ref "R14") (pin "4") (pinfunction "4_4") (pintype "bidirectional"))
    )
    (net (code "22") (name "IBN") (class "Default")
      (node (ref "C5") (pin "2") (pinfunction "2_2") (pintype "passive"))
      (node (ref "IC1") (pin "6") (pinfunction "I2N_6") (pintype "input"))
      (node (ref "R3") (pin "5") (pinfunction "5_5") (pintype "bidirectional"))
    )
    (net (code "23") (name "IBN-2") (class "Default")
      (node (ref "C20") (pin "2") (pinfunction "2_2") (pintype "passive"))
      (node (ref "IC2") (pin "6") (pinfunction "I2N_6") (pintype "input"))
      (node (ref "R14") (pin "5") (pinfunction "5_5") (pintype "bidirectional"))
    )
    (net (code "24") (name "IBP") (class "Default")
      (node (ref "C4") (pin "1") (pinfunction "1_1") (pintype "passive"))
      (node (ref "IC1") (pin "5") (pinfunction "I2P_5") (pintype "input"))
      (node (ref "R3") (pin "6") (pinfunction "6_6") (pintype "bidirectional"))
    )
    (net (code "25") (name "IBP-2") (class "Default")
      (node (ref "C19") (pin "1") (pinfunction "1_1") (pintype "passive"))
      (node (ref "IC2") (pin "5") (pinfunction "I2P_5") (pintype "input"))
      (node (ref "R14") (pin "6") (pinfunction "6_6") (pintype "bidirectional"))
    )
    (net (code "26") (name "IC+") (class "Default")
      (node (ref "CT3") (pin "2") (pinfunction "2_2") (pintype "passive"))
      (node (ref "CT3-2") (pin "2") (pinfunction "TIP_2") (pintype "passive"))
      (node (ref "J9") (pin "8") (pinfunction "8_8") (pintype "bidirectional"))
      (node (ref "R4") (pin "2") (pinfunction "2_2") (pintype "passive"))
      (node (ref "R6") (pin "2") (pinfunction "2_2") (pintype "passive"))
    )
    (net (code "27") (name "IC+-2") (class "Default")
      (node (ref "CT6") (pin "2") (pinfunction "2_2") (pintype "passive"))
      (node (ref "CT6-2") (pin "2") (pinfunction "TIP_2") (pintype "passive"))
      (node (ref "J9") (pin "18") (pinfunction "18_18") (pintype "bidirectional"))
      (node (ref "R15") (pin "2") (pinfunction "2_2") (pintype "passive"))
      (node (ref "R17") (pin "2") (pinfunction "2_2") (pintype "passive"))
    )
    (net (code "28") (name "IC-") (class "Default")
      (node (ref "CT3") (pin "1") (pinfunction "1_1") (pintype "passive"))
      (node (ref "CT3-2") (pin "1") (pinfunction "SLEEVE_1") (pintype "passive"))
      (node (ref "J9") (pin "9") (pinfunction "9_9") (pintype "bidirectional"))
      (node (ref "JP3") (pin "2") (pinfunction "2_2") (pintype "passive"))
      (node (ref "R5") (pin "2") (pinfunction "2_2") (pintype "passive"))
    )
    (net (code "29") (name "IC--2") (class "Default")
      (node (ref "CT6") (pin "1") (pinfunction "1_1") (pintype "passive"))
      (node (ref "CT6-2") (pin "1") (pinfunction "SLEEVE_1") (pintype "passive"))
      (node (ref "J9") (pin "17") (pinfunction "17_17") (pintype "bidirectional"))
      (node (ref "JP6") (pin "2") (pinfunction "2_2") (pintype "passive"))
      (node (ref "R16") (pin "2") (pinfunction "2_2") (pintype "passive"))
    )
    (net (code "30") (name "ICN") (class "Default")
      (node (ref "C7") (pin "2") (pinfunction "2_2") (pintype "passive"))
      (node (ref "IC1") (pin "8") (pinfunction "I3N_8") (pintype "input"))
      (node (ref "R5") (pin "1") (pinfunction "1_1") (pintype "passive"))
    )
    (net (code "31") (name "ICN-2") (class "Default")
      (node (ref "C22") (pin "2") (pinfunction "2_2") (pintype "passive"))
      (node (ref "IC2") (pin "8") (pinfunction "I3N_8") (pintype "input"))
      (node (ref "R16") (pin "1") (pinfunction "1_1") (pintype "passive"))
    )
    (net (code "32") (name "ICP") (class "Default")
      (node (ref "C6") (pin "1") (pinfunction "1_1") (pintype "passive"))
      (node (ref "IC1") (pin "7") (pinfunction "I3P_7") (pintype "input"))
      (node (ref "R4") (pin "1") (pinfunction "1_1") (pintype "passive"))
    )
    (net (code "33") (name "ICP-2") (class "Default")
      (node (ref "C21") (pin "1") (pinfunction "1_1") (pintype "passive"))
      (node (ref "IC2") (pin "7") (pinfunction "I3P_7") (pintype "input"))
      (node (ref "R15") (pin "1") (pinfunction "1_1") (pintype "passive"))
    )
    (net (code "34") (name "IO0") (class "Default")
      (node (ref "J4") (pin "12") (pinfunction "12_12") (pintype "bidirectional"))
      (node (ref "U1") (pin "33") (pinfunction "IO0_33") (pintype "bidirectional"))
    )
    (net (code "35") (name "IO2") (class "Default")
      (node (ref "J4") (pin "10") (pinfunction "10_10") (pintype "bidirectional"))
      (node (ref "U1") (pin "34") (pinfunction "IO2_34") (pintype "bidirectional"))
    )
    (net (code "36") (name "IO12") (class "Default")
      (node (ref "J16") (pin "13") (pinfunction "13_13") (pintype "passive"))
      (node (ref "U1") (pin "13") (pinfunction "IO12_13") (pintype "bidirectional"))
    )
    (net (code "37") (name "IO13") (class "Default")
      (node (ref "J16") (pin "15") (pinfunction "15_15") (pintype "passive"))
      (node (ref "J4") (pin "9") (pinfunction "9_9") (pintype "bidirectional"))
      (node (ref "U1") (pin "15") (pinfunction "IO13_15") (pintype "bidirectional"))
    )
    (net (code "38") (name "IO14") (class "Default")
      (node (ref "J16") (pin "12") (pinfunction "12_12") (pintype "passive"))
      (node (ref "J4") (pin "8") (pinfunction "8_8") (pintype "bidirectional"))
      (node (ref "U1") (pin "12") (pinfunction "IO14_12") (pintype "bidirectional"))
    )
    (net (code "39") (name "IO15") (class "Default")
      (node (ref "J4") (pin "7") (pinfunction "7_7") (pintype "bidirectional"))
      (node (ref "U1") (pin "35") (pinfunction "IO15_35") (pintype "bidirectional"))
    )
    (net (code "40") (name "IO16") (class "Default")
      (node (ref "J7") (pin "12") (pinfunction "12_12") (pintype "bidirectional"))
      (node (ref "U1") (pin "31") (pinfunction "IO16_31") (pintype "bidirectional"))
    )
    (net (code "41") (name "IO17") (class "Default")
      (node (ref "J7") (pin "11") (pinfunction "11_11") (pintype "bidirectional"))
      (node (ref "U1") (pin "30") (pinfunction "IO17_30") (pintype "bidirectional"))
    )
    (net (code "42") (name "IO21") (class "Default")
      (node (ref "J7") (pin "10") (pinfunction "10_10") (pintype "bidirectional"))
      (node (ref "U1") (pin "25") (pinfunction "IO21_25") (pintype "bidirectional"))
    )
    (net (code "43") (name "IO22") (class "Default")
      (node (ref "J7") (pin "9") (pinfunction "9_9") (pintype "bidirectional"))
      (node (ref "U1") (pin "22") (pinfunction "IO22_22") (pintype "bidirectional"))
    )
    (net (code "44") (name "IO25") (class "Default")
      (node (ref "J16") (pin "9") (pinfunction "9_9") (pintype "passive"))
      (node (ref "J7") (pin "8") (pinfunction "8_8") (pintype "bidirectional"))
      (node (ref "U1") (pin "9") (pinfunction "IO25_9") (pintype "bidirectional"))
    )
    (net (code "45") (name "IO26") (class "Default")
      (node (ref "J16") (pin "10") (pinfunction "10_10") (pintype "passive"))
      (node (ref "J7") (pin "7") (pinfunction "7_7") (pintype "bidirectional"))
      (node (ref "U1") (pin "10") (pinfunction "IO26_10") (pintype "bidirectional"))
    )
    (net (code "46") (name "IO27") (class "Default")
      (node (ref "J16") (pin "11") (pinfunction "11_11") (pintype "passive"))
      (node (ref "J4") (pin "11") (pinfunction "11_11") (pintype "bidirectional"))
      (node (ref "U1") (pin "11") (pinfunction "IO27_11") (pintype "bidirectional"))
    )
    (net (code "47") (name "IO35") (class "Default")
      (node (ref "J16") (pin "6") (pinfunction "6_6") (pintype "passive"))
      (node (ref "U1") (pin "6") (pinfunction "IO35_6") (pintype "bidirectional"))
    )
    (net (code "48") (name "IRQ0") (class "Default")
      (node (ref "IC1") (pin "30") (pinfunction "IRQ0_30") (pintype "output"))
      (node (ref "IC2") (pin "30") (pinfunction "IRQ0_30") (pintype "output"))
      (node (ref "J16") (pin "7") (pinfunction "7_7") (pintype "passive"))
      (node (ref "U1") (pin "7") (pinfunction "IO32_7") (pintype "bidirectional"))
    )
    (net (code "49") (name "IRQ1") (class "Default")
      (node (ref "IC1") (pin "31") (pinfunction "IRQ1_31") (pintype "output"))
      (node (ref "IC2") (pin "31") (pinfunction "IRQ1_31") (pintype "output"))
      (node (ref "J16") (pin "8") (pinfunction "8_8") (pintype "passive"))
      (node (ref "U1") (pin "8") (pinfunction "IO33_8") (pintype "bidirectional"))
    )
    (net (code "50") (name "MISO") (class "Default")
      (node (ref "IC1") (pin "39") (pinfunction "SDO_39") (pintype "output"))
      (node (ref "IC2") (pin "39") (pinfunction "SDO_39") (pintype "output"))
      (node (ref "R13") (pin "2") (pinfunction "2_2") (pintype "bidirectional"))
      (node (ref "R2") (pin "2") (pinfunction "2_2") (pintype "bidirectional"))
      (node (ref "U1") (pin "27") (pinfunction "IO19_27") (pintype "bidirectional"))
    )
    (net (code "51") (name "MOSI") (class "Default")
      (node (ref "IC1") (pin "40") (pinfunction "SDI_40") (pintype "input"))
      (node (ref "IC2") (pin "40") (pinfunction "SDI_40") (pintype "input"))
      (node (ref "R13") (pin "1") (pinfunction "1_1") (pintype "bidirectional"))
      (node (ref "R2") (pin "1") (pinfunction "1_1") (pintype "bidirectional"))
      (node (ref "U1") (pin "21") (pinfunction "IO23_21") (pintype "bidirectional"))
    )
    (net (code "52") (name "Net-(C8-Pad2)") (class "Default")
      (node (ref "C8") (pin "2") (pinfunction "2_2") (pintype "passive"))
      (node (ref "C9") (pin "2") (pinfunction "2_2") (pintype "passive"))
      (node (ref "IC1") (pin "42") (pinfunction "VDD18_42") (pintype "power_in"))
      (node (ref "IC1") (pin "43") (pinfunction "VDD18_43") (pintype "power_in"))
    )
    (net (code "53") (name "Net-(C23-Pad2)") (class "Default")
      (node (ref "C23") (pin "2") (pinfunction "2_2") (pintype "passive"))
      (node (ref "C24") (pin "2") (pinfunction "2_2") (pintype "passive"))
      (node (ref "IC2") (pin "42") (pinfunction "VDD18_42") (pintype "power_in"))
      (node (ref "IC2") (pin "43") (pinfunction "VDD18_43") (pintype "power_in"))
    )
    (net (code "54") (name "Net-(CF1-2-PadA)") (class "Default")
      (node (ref "CF1-2") (pin "A") (pinfunction "A_A") (pintype "passive"))
      (node (ref "R20") (pin "1") (pinfunction "1_1") (pintype "passive"))
    )
    (net (code "55") (name "Net-(CF1-PadA)") (class "Default")
      (node (ref "CF1") (pin "A") (pinfunction "A_A") (pintype "passive"))
      (node (ref "R9") (pin "1") (pinfunction "1_1") (pintype "passive"))
    )
    (net (code "56") (name "Net-(IC1-OSCI)") (class "Default")
      (node (ref "IC1") (pin "20") (pinfunction "OSCI_20") (pintype "input"))
      (node (ref "Y1") (pin "1") (pinfunction "1_1") (pintype "passive"))
    )
    (net (code "57") (name "Net-(IC1-OSCO)") (class "Default")
      (node (ref "IC1") (pin "21") (pinfunction "OSCO_21") (pintype "output"))
      (node (ref "Y1") (pin "3") (pinfunction "2_3") (pintype "passive"))
    )
    (net (code "58") (name "Net-(IC1-VREF)") (class "Default")
      (node (ref "C12") (pin "1") (pinfunction "1_1") (pintype "passive"))
      (node (ref "C13") (pin "1") (pinfunction "1_1") (pintype "passive"))
      (node (ref "IC1") (pin "11") (pinfunction "VREF_11") (pintype "bidirectional"))
    )
    (net (code "59") (name "Net-(IC1-~{RESET})") (class "Default")
      (node (ref "C1") (pin "2") (pinfunction "2_2") (pintype "passive"))
      (node (ref "IC1") (pin "41") (pinfunction "~{RESET}_41") (pintype "input"))
      (node (ref "R1") (pin "2") (pinfunction "2_2") (pintype "passive"))
    )
    (net (code "60") (name "Net-(IC2-OSCI)") (class "Default")
      (node (ref "IC2") (pin "20") (pinfunction "OSCI_20") (pintype "input"))
      (node (ref "Y2") (pin "1") (pinfunction "1_1") (pintype "passive"))
    )
    (net (code "61") (name "Net-(IC2-OSCO)") (class "Default")
      (node (ref "IC2") (pin "21") (pinfunction "OSCO_21") (pintype "output"))
      (node (ref "Y2") (pin "3") (pinfunction "2_3") (pintype "passive"))
    )
    (net (code "62") (name "Net-(IC2-VREF)") (class "Default")
      (node (ref "C27") (pin "1") (pinfunction "1_1") (pintype "passive"))
      (node (ref "C28") (pin "1") (pinfunction "1_1") (pintype "passive"))
      (node (ref "IC2") (pin "11") (pinfunction "VREF_11") (pintype "bidirectional"))
    )
    (net (code "63") (name "Net-(IC2-~{RESET})") (class "Default")
      (node (ref "C16") (pin "2") (pinfunction "2_2") (pintype "passive"))
      (node (ref "IC2") (pin "41") (pinfunction "~{RESET}_41") (pintype "input"))
      (node (ref "R12") (pin "2") (pinfunction "2_2") (pintype "passive"))
    )
    (net (code "64") (name "Net-(JP1-Pad1)") (class "Default")
      (node (ref "JP1") (pin "1") (pinfunction "1_1") (pintype "passive"))
      (node (ref "R7") (pin "1") (pinfunction "1_1") (pintype "passive"))
    )
    (net (code "65") (name "Net-(JP2-Pad1)") (class "Default")
      (node (ref "JP2") (pin "1") (pinfunction "1_1") (pintype "passive"))
      (node (ref "R8") (pin "1") (pinfunction "1_1") (pintype "passive"))
    )
    (net (code "66") (name "Net-(JP3-Pad1)") (class "Default")
      (node (ref "JP3") (pin "1") (pinfunction "1_1") (pintype "passive"))
      (node (ref "R6") (pin "1") (pinfunction "1_1") (pintype "passive"))
    )
    (net (code "67") (name "Net-(JP4-Pad1)") (class "Default")
      (node (ref "JP4") (pin "1") (pinfunction "1_1") (pintype "passive"))
      (node (ref "R18") (pin "1") (pinfunction "1_1") (pintype "passive"))
    )
    (net (code "68") (name "Net-(JP5-Pad1)") (class "Default")
      (node (ref "JP5") (pin "1") (pinfunction "1_1") (pintype "passive"))
      (node (ref "R19") (pin "1") (pinfunction "1_1") (pintype "passive"))
    )
    (net (code "69") (name "Net-(JP6-Pad1)") (class "Default")
      (node (ref "JP6") (pin "1") (pinfunction "1_1") (pintype "passive"))
      (node (ref "R17") (pin "1") (pinfunction "1_1") (pintype "passive"))
    )
    (net (code "70") (name "Net-(PWR-PadA)") (class "Default")
      (node (ref "PWR") (pin "A") (pinfunction "A_A") (pintype "passive"))
      (node (ref "R10") (pin "1") (pinfunction "1_1") (pintype "passive"))
    )
    (net (code "71") (name "Net-(U1-CMD)") (class "Default")
      (node (ref "J16") (pin "18") (pinfunction "18_18") (pintype "passive"))
      (node (ref "U1") (pin "18") (pinfunction "CMD_18") (pintype "bidirectional"))
    )
    (net (code "72") (name "Net-(U1-EN)") (class "Default")
      (node (ref "J16") (pin "2") (pinfunction "2_2") (pintype "passive"))
      (node (ref "U1") (pin "2") (pinfunction "EN_2") (pintype "input"))
    )
    (net (code "73") (name "Net-(U1-EXT_5V)") (class "Default")
      (node (ref "J16") (pin "19") (pinfunction "19_19") (pintype "passive"))
      (node (ref "U1") (pin "19") (pinfunction "EXT_5V_19") (pintype "power_in"))
    )
    (net (code "74") (name "Net-(U1-SD2)") (class "Default")
      (node (ref "J16") (pin "16") (pinfunction "16_16") (pintype "passive"))
      (node (ref "U1") (pin "16") (pinfunction "SD2_16") (pintype "bidirectional"))
    )
    (net (code "75") (name "Net-(U1-SD3)") (class "Default")
      (node (ref "J16") (pin "17") (pinfunction "17_17") (pintype "passive"))
      (node (ref "U1") (pin "17") (pinfunction "SD3_17") (pintype "bidirectional"))
    )
    (net (code "76") (name "Net-(U1-SENSOR_VN)") (class "Default")
      (node (ref "J16") (pin "4") (pinfunction "4_4") (pintype "passive"))
      (node (ref "U1") (pin "4") (pinfunction "SENSOR_VN_4") (pintype "input"))
    )
    (net (code "77") (name "Net-(U1-SENSOR_VP)") (class "Default")
      (node (ref "J16") (pin "3") (pinfunction "3_3") (pintype "passive"))
      (node (ref "U1") (pin "3") (pinfunction "SENSOR_VP_3") (pintype "input"))
    )
    (net (code "78") (name "SCLK") (class "Default")
      (node (ref "IC1") (pin "38") (pinfunction "SCLK_38") (pintype "input"))
      (node (ref "IC2") (pin "38") (pinfunction "SCLK_38") (pintype "input"))
      (node (ref "R13") (pin "3") (pinfunction "3_3") (pintype "bidirectional"))
      (node (ref "R2") (pin "3") (pinfunction "3_3") (pintype "bidirectional"))
      (node (ref "U1") (pin "28") (pinfunction "IO18_28") (pintype "bidirectional"))
    )
    (net (code "79") (name "VA+") (class "Default")
      (node (ref "J8") (pin "1") (pinfunction "1_1") (pintype "passive"))
      (node (ref "JP12") (pin "2") (pinfunction "2_2") (pintype "passive"))
      (node (ref "R26") (pin "2") (pinfunction "2_2") (pintype "passive"))
    )
    (net (code "80") (name "VA-") (class "Default")
      (node (ref "J6") (pin "1") (pinfunction "1_1") (pintype "passive"))
      (node (ref "JP13") (pin "2") (pinfunction "2_2") (pintype "passive"))
      (node (ref "R34") (pin "2") (pinfunction "2_2") (pintype "passive"))
    )
    (net (code "81") (name "VA2+") (class "Default")
      (node (ref "J3") (pin "2") (pinfunction "2_2") (pintype "passive"))
      (node (ref "JP12") (pin "1") (pinfunction "1_1") (pintype "passive"))
      (node (ref "R28") (pin "2") (pinfunction "2_2") (pintype "passive"))
    )
    (net (code "82") (name "VA2-") (class "Default")
      (node (ref "J3") (pin "1") (pinfunction "1_1") (pintype "passive"))
      (node (ref "JP13") (pin "1") (pinfunction "1_1") (pintype "passive"))
      (node (ref "R32") (pin "2") (pinfunction "2_2") (pintype "passive"))
    )
    (net (code "83") (name "VAN") (class "Default")
      (node (ref "C15") (pin "1") (pinfunction "1_1") (pintype "passive"))
      (node (ref "IC1") (pin "14") (pinfunction "V1N_14") (pintype "input"))
      (node (ref "IC1") (pin "16") (pinfunction "V2N_16") (pintype "input"))
      (node (ref "IC1") (pin "18") (pinfunction "V3N_18") (pintype "input"))
      (node (ref "R11") (pin "6") (pinfunction "6_6") (pintype "bidirectional"))
      (node (ref "R24") (pin "7") (pinfunction "7_7") (pintype "bidirectional"))
      (node (ref "R34") (pin "1") (pinfunction "1_1") (pintype "passive"))
    )
    (net (code "84") (name "VAN2") (class "Default")
      (node (ref "C30") (pin "1") (pinfunction "1_1") (pintype "passive"))
      (node (ref "IC2") (pin "14") (pinfunction "V1N_14") (pintype "input"))
      (node (ref "IC2") (pin "16") (pinfunction "V2N_16") (pintype "input"))
      (node (ref "IC2") (pin "18") (pinfunction "V3N_18") (pintype "input"))
      (node (ref "R11") (pin "5") (pinfunction "5_5") (pintype "bidirectional"))
      (node (ref "R24") (pin "8") (pinfunction "8_8") (pintype "bidirectional"))
      (node (ref "R32") (pin "1") (pinfunction "1_1") (pintype "passive"))
    )
    (net (code "85") (name "VAP") (class "Default")
      (node (ref "C14") (pin "1") (pinfunction "1_1") (pintype "passive"))
      (node (ref "IC1") (pin "13") (pinfunction "V1P_13") (pintype "input"))
      (node (ref "IC1") (pin "15") (pinfunction "V2P_15") (pintype "input"))
      (node (ref "IC1") (pin "17") (pinfunction "V3P_17") (pintype "input"))
      (node (ref "R11") (pin "7") (pinfunction "7_7") (pintype "bidirectional"))
      (node (ref "R24") (pin "6") (pinfunction "6_6") (pintype "bidirectional"))
      (node (ref "R26") (pin "1") (pinfunction "1_1") (pintype "passive"))
    )
    (net (code "86") (name "VAP2") (class "Default")
      (node (ref "C29") (pin "1") (pinfunction "1_1") (pintype "passive"))
      (node (ref "IC2") (pin "13") (pinfunction "V1P_13") (pintype "input"))
      (node (ref "IC2") (pin "15") (pinfunction "V2P_15") (pintype "input"))
      (node (ref "IC2") (pin "17") (pinfunction "V3P_17") (pintype "input"))
      (node (ref "R11") (pin "8") (pinfunction "8_8") (pintype "bidirectional"))
      (node (ref "R24") (pin "5") (pinfunction "5_5") (pintype "bidirectional"))
      (node (ref "R28") (pin "1") (pinfunction "1_1") (pintype "passive"))
    )
    (net (code "87") (name "VDD") (class "Default")
      (node (ref "C10") (pin "2") (pinfunction "2_2") (pintype "passive"))
      (node (ref "C11") (pin "2") (pinfunction "2_2") (pintype "passive"))
      (node (ref "C25") (pin "2") (pinfunction "2_2") (pintype "passive"))
      (node (ref "C26") (pin "2") (pinfunction "2_2") (pintype "passive"))
      (node (ref "C36") (pin "1") (pinfunction "1_1") (pintype "passive"))
      (node (ref "IC1") (pin "1") (pinfunction "AVDD_1") (pintype "power_in"))
      (node (ref "IC1") (pin "33") (pinfunction "PM0_33") (pintype "input"))
      (node (ref "IC1") (pin "34") (pinfunction "PM1_34") (pintype "input"))
      (node (ref "IC1") (pin "48") (pinfunction "DVDD_48") (pintype "power_in"))
      (node (ref "IC2") (pin "1") (pinfunction "AVDD_1") (pintype "power_in"))
      (node (ref "IC2") (pin "33") (pinfunction "PM0_33") (pintype "input"))
      (node (ref "IC2") (pin "34") (pinfunction "PM1_34") (pintype "input"))
      (node (ref "IC2") (pin "48") (pinfunction "DVDD_48") (pintype "power_in"))
      (node (ref "J16") (pin "1") (pinfunction "1_1") (pintype "passive"))
      (node (ref "R1") (pin "1") (pinfunction "1_1") (pintype "passive"))
      (node (ref "R10") (pin "2") (pinfunction "2_2") (pintype "passive"))
      (node (ref "R12") (pin "1") (pinfunction "1_1") (pintype "passive"))
      (node (ref "R13") (pin "5") (pinfunction "5_5") (pintype "bidirectional"))
      (node (ref "R13") (pin "6") (pinfunction "6_6") (pintype "bidirectional"))
      (node (ref "R13") (pin "7") (pinfunction "7_7") (pintype "bidirectional"))
      (node (ref "R13") (pin "8") (pinfunction "8_8") (pintype "bidirectional"))
      (node (ref "R2") (pin "5") (pinfunction "5_5") (pintype "bidirectional"))
      (node (ref "R2") (pin "6") (pinfunction "6_6") (pintype "bidirectional"))
      (node (ref "R2") (pin "7") (pinfunction "7_7") (pintype "bidirectional"))
      (node (ref "R2") (pin "8") (pinfunction "8_8") (pintype "bidirectional"))
      (node (ref "R24") (pin "1") (pinfunction "1_1") (pintype "bidirectional"))
      (node (ref "R24") (pin "2") (pinfunction "2_2") (pintype "bidirectional"))
      (node (ref "R24") (pin "3") (pinfunction "3_3") (pintype "bidirectional"))
      (node (ref "R24") (pin "4") (pinfunction "4_4") (pintype "bidirectional"))
      (node (ref "U1") (pin "1") (pinfunction "3V3_1") (pintype "power_in"))
    )
    (net (code "88") (name "WARN") (class "Default")
      (node (ref "IC1") (pin "29") (pinfunction "WARNOUT_29") (pintype "output"))
      (node (ref "IC2") (pin "29") (pinfunction "WARNOUT_29") (pintype "output"))
      (node (ref "J16") (pin "5") (pinfunction "5_5") (pintype "passive"))
      (node (ref "U1") (pin "5") (pinfunction "IO34_5") (pintype "bidirectional"))
    )
    (net (code "89") (name "ZX0") (class "Default")
      (node (ref "IC1") (pin "22") (pinfunction "ZX0_22") (pintype "output"))
      (node (ref "ZX0") (pin "1") (pinfunction "P_1") (pintype "passive"))
    )
    (net (code "90") (name "ZX0-2") (class "Default")
      (node (ref "IC2") (pin "22") (pinfunction "ZX0_22") (pintype "output"))
      (node (ref "ZX0-2") (pin "1") (pinfunction "P_1") (pintype "passive"))
    )
    (net (code "91") (name "ZX1") (class "Default")
      (node (ref "IC1") (pin "23") (pinfunction "ZX1_23") (pintype "output"))
      (node (ref "ZX1") (pin "1") (pinfunction "P_1") (pintype "passive"))
    )
    (net (code "92") (name "ZX1-2") (class "Default")
      (node (ref "IC2") (pin "23") (pinfunction "ZX1_23") (pintype "output"))
      (node (ref "ZX1-2") (pin "1") (pinfunction "P_1") (pintype "passive"))
    )
    (net (code "93") (name "ZX2") (class "Default")
      (node (ref "IC1") (pin "24") (pinfunction "ZX2_24") (pintype "output"))
      (node (ref "ZX2") (pin "1") (pinfunction "P_1") (pintype "passive"))
    )
    (net (code "94") (name "ZX2-2") (class "Default")
      (node (ref "IC2") (pin "24") (pinfunction "ZX2_24") (pintype "output"))
      (node (ref "ZX2-2") (pin "1") (pinfunction "P_1") (pintype "passive"))
    )
    (net (code "95") (name "unconnected-(CT1-2-RING-Pad3)") (class "Default")
      (node (ref "CT1-2") (pin "3") (pinfunction "RING_3") (pintype "passive"))
    )
    (net (code "96") (name "unconnected-(CT1-2-TIP_SWITCH-Pad10)") (class "Default")
      (node (ref "CT1-2") (pin "10") (pinfunction "TIP_SWITCH_10") (pintype "passive"))
    )
    (net (code "97") (name "unconnected-(CT2-2-RING-Pad3)") (class "Default")
      (node (ref "CT2-2") (pin "3") (pinfunction "RING_3") (pintype "passive"))
    )
    (net (code "98") (name "unconnected-(CT2-2-TIP_SWITCH-Pad10)") (class "Default")
      (node (ref "CT2-2") (pin "10") (pinfunction "TIP_SWITCH_10") (pintype "passive"))
    )
    (net (code "99") (name "unconnected-(CT3-2-RING-Pad3)") (class "Default")
      (node (ref "CT3-2") (pin "3") (pinfunction "RING_3") (pintype "passive"))
    )
    (net (code "100") (name "unconnected-(CT3-2-TIP_SWITCH-Pad10)") (class "Default")
      (node (ref "CT3-2") (pin "10") (pinfunction "TIP_SWITCH_10") (pintype "passive"))
    )
    (net (code "101") (name "unconnected-(CT4-2-RING-Pad3)") (class "Default")
      (node (ref "CT4-2") (pin "3") (pinfunction "RING_3") (pintype "passive"))
    )
    (net (code "102") (name "unconnected-(CT4-2-TIP_SWITCH-Pad10)") (class "Default")
      (node (ref "CT4-2") (pin "10") (pinfunction "TIP_SWITCH_10") (pintype "passive"))
    )
    (net (code "103") (name "unconnected-(CT5-2-RING-Pad3)") (class "Default")
      (node (ref "CT5-2") (pin "3") (pinfunction "RING_3") (pintype "passive"))
    )
    (net (code "104") (name "unconnected-(CT5-2-TIP_SWITCH-Pad10)") (class "Default")
      (node (ref "CT5-2") (pin "10") (pinfunction "TIP_SWITCH_10") (pintype "passive"))
    )
    (net (code "105") (name "unconnected-(CT6-2-RING-Pad3)") (class "Default")
      (node (ref "CT6-2") (pin "3") (pinfunction "RING_3") (pintype "passive"))
    )
    (net (code "106") (name "unconnected-(CT6-2-TIP_SWITCH-Pad10)") (class "Default")
      (node (ref "CT6-2") (pin "10") (pinfunction "TIP_SWITCH_10") (pintype "passive"))
    )
    (net (code "107") (name "unconnected-(IC1-I4N-Pad10)") (class "Default")
      (node (ref "IC1") (pin "10") (pinfunction "I4N_10") (pintype "input"))
    )
    (net (code "108") (name "unconnected-(IC1-I4P-Pad9)") (class "Default")
      (node (ref "IC1") (pin "9") (pinfunction "I4P_9") (pintype "input"))
    )
    (net (code "109") (name "unconnected-(IC1-NC-Pad35)") (class "Default")
      (node (ref "IC1") (pin "35") (pinfunction "NC_35") (pintype "no_connect"))
    )
    (net (code "110") (name "unconnected-(IC1-NC-Pad45)") (class "Default")
      (node (ref "IC1") (pin "45") (pinfunction "NC_45") (pintype "no_connect"))
    )
    (net (code "111") (name "unconnected-(IC1-NC-Pad46)") (class "Default")
      (node (ref "IC1") (pin "46") (pinfunction "NC_46") (pintype "no_connect"))
    )
    (net (code "112") (name "unconnected-(IC2-I4N-Pad10)") (class "Default")
      (node (ref "IC2") (pin "10") (pinfunction "I4N_10") (pintype "input"))
    )
    (net (code "113") (name "unconnected-(IC2-I4P-Pad9)") (class "Default")
      (node (ref "IC2") (pin "9") (pinfunction "I4P_9") (pintype "input"))
    )
    (net (code "114") (name "unconnected-(IC2-NC-Pad35)") (class "Default")
      (node (ref "IC2") (pin "35") (pinfunction "NC_35") (pintype "no_connect"))
    )
    (net (code "115") (name "unconnected-(IC2-NC-Pad45)") (class "Default")
      (node (ref "IC2") (pin "45") (pinfunction "NC_45") (pintype "no_connect"))
    )
    (net (code "116") (name "unconnected-(IC2-NC-Pad46)") (class "Default")
      (node (ref "IC2") (pin "46") (pinfunction "NC_46") (pintype "no_connect"))
    )
    (net (code "117") (name "unconnected-(J5-Pad1)") (class "Default")
      (node (ref "J5") (pin "1") (pinfunction "1_1") (pintype "passive"))
    )
    (net (code "118") (name "unconnected-(U1-CLK-Pad38)") (class "Default")
      (node (ref "U1") (pin "38") (pinfunction "CLK_38") (pintype "input"))
    )
    (net (code "119") (name "unconnected-(U1-IO4-Pad32)") (class "Default")
      (node (ref "U1") (pin "32") (pinfunction "IO4_32") (pintype "bidirectional"))
    )
    (net (code "120") (name "unconnected-(U1-IO5-Pad29)") (class "Default")
      (node (ref "U1") (pin "29") (pinfunction "IO5_29") (pintype "bidirectional"))
    )
    (net (code "121") (name "unconnected-(U1-RXD0-Pad24)") (class "Default")
      (node (ref "U1") (pin "24") (pinfunction "RXD0_24") (pintype "input"))
    )
    (net (code "122") (name "unconnected-(U1-SD0-Pad37)") (class "Default")
      (node (ref "U1") (pin "37") (pinfunction "SD0_37") (pintype "bidirectional"))
    )
    (net (code "123") (name "unconnected-(U1-SD1-Pad36)") (class "Default")
      (node (ref "U1") (pin "36") (pinfunction "SD1_36") (pintype "bidirectional"))
    )
    (net (code "124") (name "unconnected-(U1-TXD0-Pad23)") (class "Default")
      (node (ref "U1") (pin "23") (pinfunction "TXD0_23") (pintype "output"))
    )
    (net (code "125") (name "~{CS-2}") (class "Default")
      (node (ref "IC2") (pin "37") (pinfunction "~{CS}_37") (pintype "input"))
      (node (ref "J7") (pin "1") (pinfunction "1_1") (pintype "bidirectional"))
      (node (ref "J7") (pin "2") (pinfunction "2_2") (pintype "bidirectional"))
      (node (ref "J7") (pin "3") (pinfunction "3_3") (pintype "bidirectional"))
      (node (ref "J7") (pin "4") (pinfunction "4_4") (pintype "bidirectional"))
      (node (ref "J7") (pin "5") (pinfunction "5_5") (pintype "bidirectional"))
      (node (ref "J7") (pin "6") (pinfunction "6_6") (pintype "bidirectional"))
      (node (ref "R13") (pin "4") (pinfunction "4_4") (pintype "bidirectional"))
    )
    (net (code "126") (name "~{CS}") (class "Default")
      (node (ref "IC1") (pin "37") (pinfunction "~{CS}_37") (pintype "input"))
      (node (ref "J4") (pin "1") (pinfunction "1_1") (pintype "bidirectional"))
      (node (ref "J4") (pin "2") (pinfunction "2_2") (pintype "bidirectional"))
      (node (ref "J4") (pin "3") (pinfunction "3_3") (pintype "bidirectional"))
      (node (ref "J4") (pin "4") (pinfunction "4_4") (pintype "bidirectional"))
      (node (ref "J4") (pin "5") (pinfunction "5_5") (pintype "bidirectional"))
      (node (ref "J4") (pin "6") (pinfunction "6_6") (pintype "bidirectional"))
      (node (ref "R2") (pin "4") (pinfunction "4_4") (pintype "bidirectional"))
    )
  )
)
